# millefori.net
KiCad netlist of a schematic drawn in EAGLE
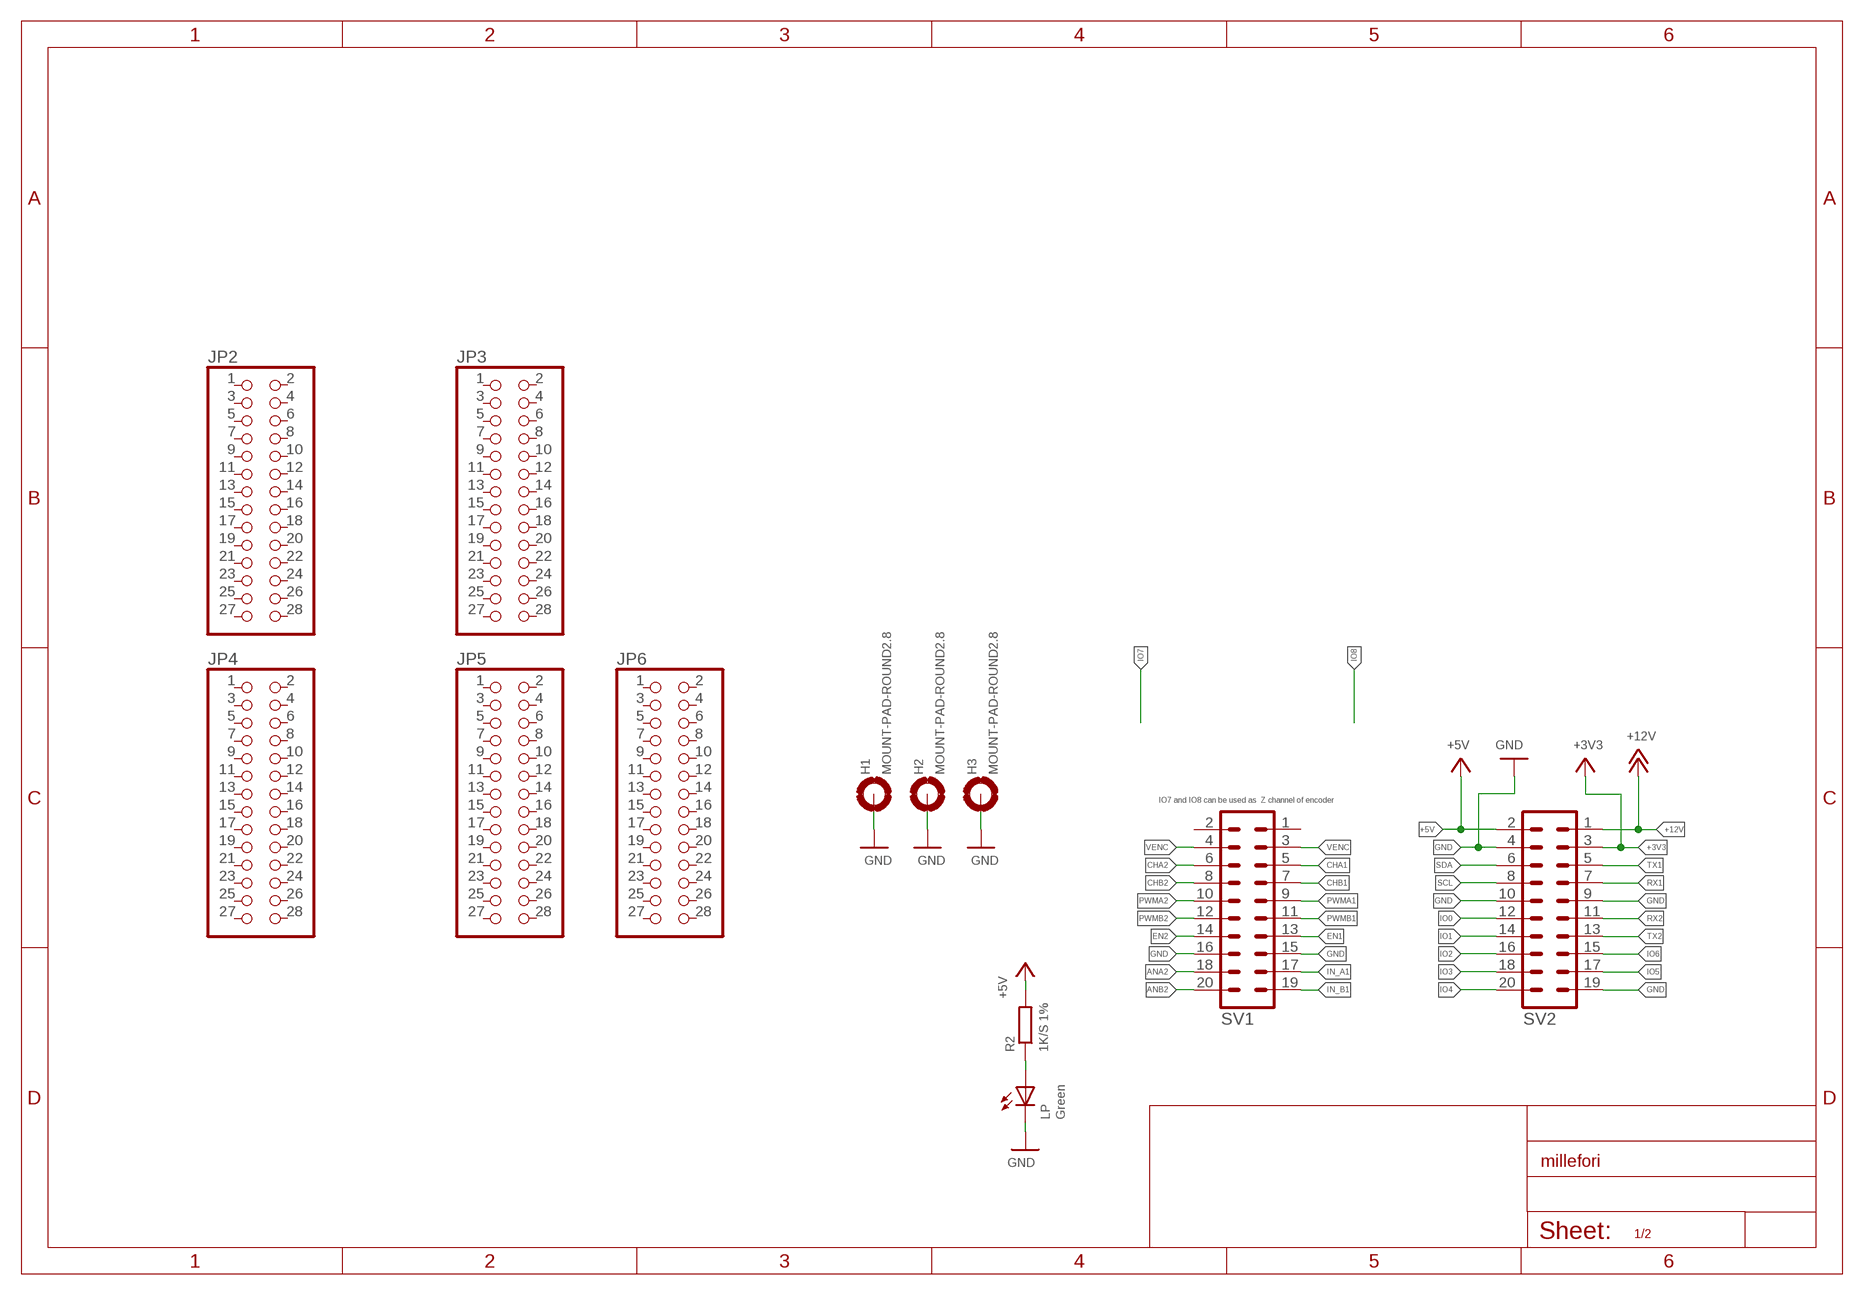
[diagram p0: schematic, sheet 1]
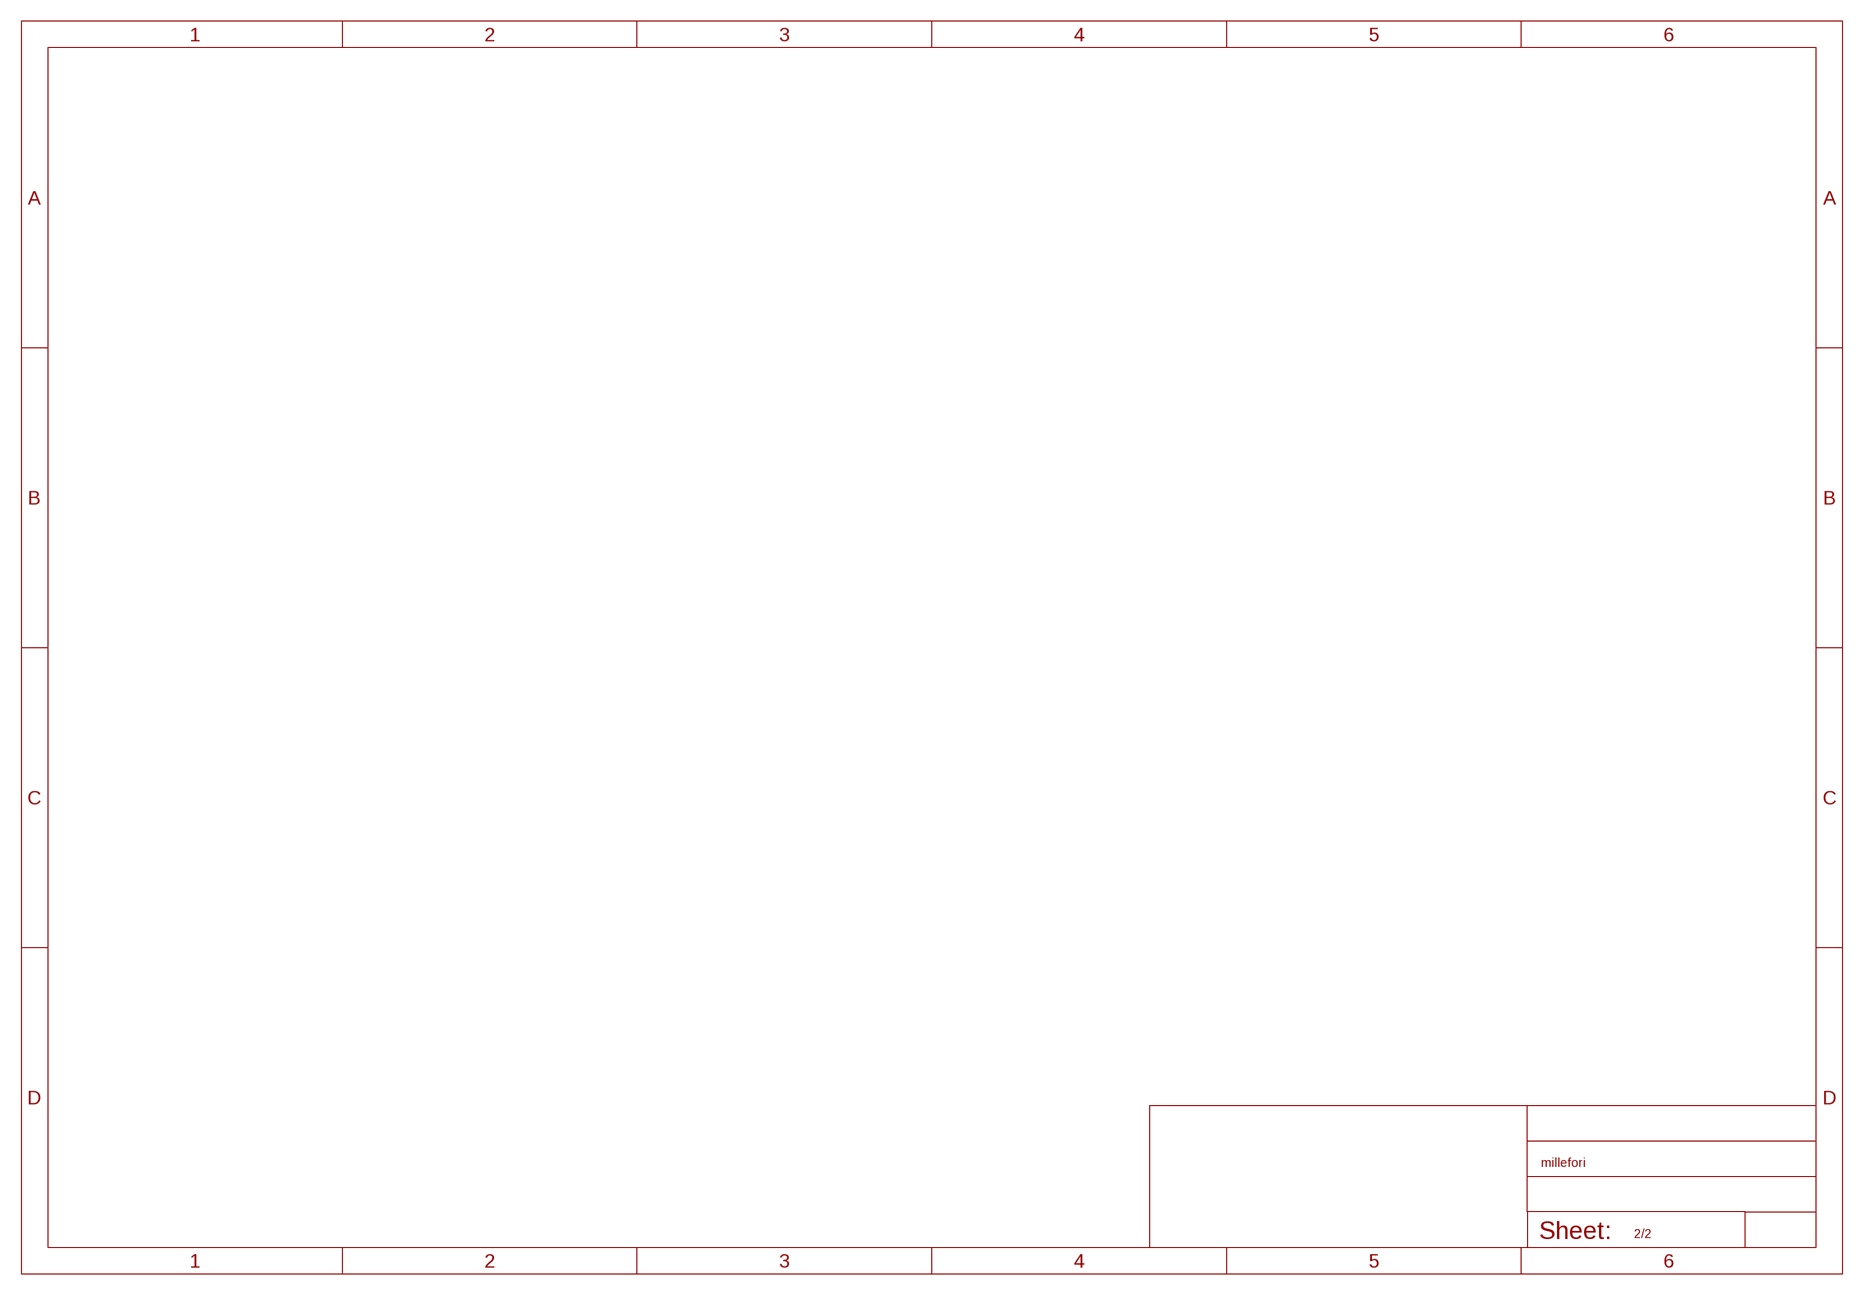
[diagram p1: schematic, sheet 2]

(export (version "E")
  (design (tool "Eeschema 10.0.6"))
  (components
    (comp (ref "H1")
      (value "MOUNT-PAD-ROUND2.8")
      (footprint "eagle-import:2,8-PAD")
      (libsource (lib "eagle-import") (part "MOUNT-PAD-ROUND2.8"))
    )
    (comp (ref "H2")
      (value "MOUNT-PAD-ROUND2.8")
      (footprint "eagle-import:2,8-PAD")
      (libsource (lib "eagle-import") (part "MOUNT-PAD-ROUND2.8"))
    )
    (comp (ref "H3")
      (value "MOUNT-PAD-ROUND2.8")
      (footprint "eagle-import:2,8-PAD")
      (libsource (lib "eagle-import") (part "MOUNT-PAD-ROUND2.8"))
    )
    (comp (ref "JP2")
      (value "PINHD-2X14")
      (footprint "eagle-import:2X14")
      (libsource (lib "eagle-import") (part "PINHD-2X14"))
    )
    (comp (ref "JP3")
      (value "PINHD-2X14")
      (footprint "eagle-import:2X14")
      (libsource (lib "eagle-import") (part "PINHD-2X14"))
    )
    (comp (ref "JP4")
      (value "PINHD-2X14")
      (footprint "eagle-import:2X14")
      (libsource (lib "eagle-import") (part "PINHD-2X14"))
    )
    (comp (ref "JP5")
      (value "PINHD-2X14")
      (footprint "eagle-import:2X14")
      (libsource (lib "eagle-import") (part "PINHD-2X14"))
    )
    (comp (ref "JP6")
      (value "PINHD-2X14")
      (footprint "eagle-import:2X14")
      (libsource (lib "eagle-import") (part "PINHD-2X14"))
    )
    (comp (ref "LP")
      (value "Green")
      (footprint "eagle-import:CHIPLED_0805")
      (libsource (lib "eagle-import") (part "LEDCHIPLED_0805"))
    )
    (comp (ref "R2")
      (value "1K/S 1%")
      (footprint "eagle-import:R0603")
      (libsource (lib "eagle-import") (part "R-EU_R0603"))
    )
    (comp (ref "SV1")
      (value "MA10-2")
      (footprint "eagle-import:MA10-2")
      (fields (field (name "OC_FARNELL") "unknown") (field (name "OC_NEWARK") "unknown"))
      (libsource (lib "eagle-import") (part "MA10-2"))
    )
    (comp (ref "SV2")
      (value "MA10-2")
      (footprint "eagle-import:MA10-2")
      (libsource (lib "eagle-import") (part "MA10-2"))
    )
  )
  (nets
    (net (code "1") (name "+3V3") (class "Default")
      (node (ref "SV2") (pin "3") (pinfunction "3_3") (pintype "passive"))
    )
    (net (code "2") (name "+5V") (class "Default")
      (node (ref "R2") (pin "2") (pinfunction "2_2") (pintype "passive"))
      (node (ref "SV2") (pin "2") (pinfunction "2_2") (pintype "passive"))
    )
    (net (code "3") (name "+12V") (class "Default")
      (node (ref "SV2") (pin "1") (pinfunction "1_1") (pintype "passive"))
    )
    (net (code "4") (name "ANA2") (class "Default")
      (node (ref "SV1") (pin "18") (pinfunction "18_18") (pintype "passive"))
    )
    (net (code "5") (name "ANB2") (class "Default")
      (node (ref "SV1") (pin "20") (pinfunction "20_20") (pintype "passive"))
    )
    (net (code "6") (name "CHA1") (class "Default")
      (node (ref "SV1") (pin "5") (pinfunction "5_5") (pintype "passive"))
    )
    (net (code "7") (name "CHA2") (class "Default")
      (node (ref "SV1") (pin "6") (pinfunction "6_6") (pintype "passive"))
    )
    (net (code "8") (name "CHB1") (class "Default")
      (node (ref "SV1") (pin "7") (pinfunction "7_7") (pintype "passive"))
    )
    (net (code "9") (name "CHB2") (class "Default")
      (node (ref "SV1") (pin "8") (pinfunction "8_8") (pintype "passive"))
    )
    (net (code "10") (name "EN1") (class "Default")
      (node (ref "SV1") (pin "13") (pinfunction "13_13") (pintype "passive"))
    )
    (net (code "11") (name "EN2") (class "Default")
      (node (ref "SV1") (pin "14") (pinfunction "14_14") (pintype "passive"))
    )
    (net (code "12") (name "GND") (class "Default")
      (node (ref "H1") (pin "B2,8") (pinfunction "MOUNT_B2,8") (pintype "passive"))
      (node (ref "H2") (pin "B2,8") (pinfunction "MOUNT_B2,8") (pintype "passive"))
      (node (ref "H3") (pin "B2,8") (pinfunction "MOUNT_B2,8") (pintype "passive"))
      (node (ref "LP") (pin "C") (pinfunction "C_C") (pintype "passive"))
      (node (ref "SV1") (pin "15") (pinfunction "15_15") (pintype "passive"))
      (node (ref "SV1") (pin "16") (pinfunction "16_16") (pintype "passive"))
      (node (ref "SV2") (pin "10") (pinfunction "10_10") (pintype "passive"))
      (node (ref "SV2") (pin "19") (pinfunction "19_19") (pintype "passive"))
      (node (ref "SV2") (pin "4") (pinfunction "4_4") (pintype "passive"))
      (node (ref "SV2") (pin "9") (pinfunction "9_9") (pintype "passive"))
    )
    (net (code "13") (name "IN_A1") (class "Default")
      (node (ref "SV1") (pin "17") (pinfunction "17_17") (pintype "passive"))
    )
    (net (code "14") (name "IN_B1") (class "Default")
      (node (ref "SV1") (pin "19") (pinfunction "19_19") (pintype "passive"))
    )
    (net (code "15") (name "IO0") (class "Default")
      (node (ref "SV2") (pin "12") (pinfunction "12_12") (pintype "passive"))
    )
    (net (code "16") (name "IO1") (class "Default")
      (node (ref "SV2") (pin "14") (pinfunction "14_14") (pintype "passive"))
    )
    (net (code "17") (name "IO2") (class "Default")
      (node (ref "SV2") (pin "16") (pinfunction "16_16") (pintype "passive"))
    )
    (net (code "18") (name "IO3") (class "Default")
      (node (ref "SV2") (pin "18") (pinfunction "18_18") (pintype "passive"))
    )
    (net (code "19") (name "IO4") (class "Default")
      (node (ref "SV2") (pin "20") (pinfunction "20_20") (pintype "passive"))
    )
    (net (code "20") (name "IO5") (class "Default")
      (node (ref "SV2") (pin "17") (pinfunction "17_17") (pintype "passive"))
    )
    (net (code "21") (name "IO6") (class "Default")
      (node (ref "SV2") (pin "15") (pinfunction "15_15") (pintype "passive"))
    )
    (net (code "24") (name "Net-(LP-PadA)") (class "Default")
      (node (ref "LP") (pin "A") (pinfunction "A_A") (pintype "passive"))
      (node (ref "R2") (pin "1") (pinfunction "1_1") (pintype "passive"))
    )
    (net (code "25") (name "PWMA1") (class "Default")
      (node (ref "SV1") (pin "9") (pinfunction "9_9") (pintype "passive"))
    )
    (net (code "26") (name "PWMA2") (class "Default")
      (node (ref "SV1") (pin "10") (pinfunction "10_10") (pintype "passive"))
    )
    (net (code "27") (name "PWMB1") (class "Default")
      (node (ref "SV1") (pin "11") (pinfunction "11_11") (pintype "passive"))
    )
    (net (code "28") (name "PWMB2") (class "Default")
      (node (ref "SV1") (pin "12") (pinfunction "12_12") (pintype "passive"))
    )
    (net (code "29") (name "RX1") (class "Default")
      (node (ref "SV2") (pin "7") (pinfunction "7_7") (pintype "passive"))
    )
    (net (code "30") (name "RX2") (class "Default")
      (node (ref "SV2") (pin "11") (pinfunction "11_11") (pintype "passive"))
    )
    (net (code "31") (name "SCL") (class "Default")
      (node (ref "SV2") (pin "8") (pinfunction "8_8") (pintype "passive"))
    )
    (net (code "32") (name "SDA") (class "Default")
      (node (ref "SV2") (pin "6") (pinfunction "6_6") (pintype "passive"))
    )
    (net (code "33") (name "TX1") (class "Default")
      (node (ref "SV2") (pin "5") (pinfunction "5_5") (pintype "passive"))
    )
    (net (code "34") (name "TX2") (class "Default")
      (node (ref "SV2") (pin "13") (pinfunction "13_13") (pintype "passive"))
    )
    (net (code "35") (name "VENC") (class "Default")
      (node (ref "SV1") (pin "3") (pinfunction "3_3") (pintype "passive"))
      (node (ref "SV1") (pin "4") (pinfunction "4_4") (pintype "passive"))
    )
    (net (code "36") (name "unconnected-(JP2-Pad1)") (class "Default")
      (node (ref "JP2") (pin "1") (pinfunction "1_1") (pintype "passive"))
    )
    (net (code "37") (name "unconnected-(JP2-Pad2)") (class "Default")
      (node (ref "JP2") (pin "2") (pinfunction "2_2") (pintype "passive"))
    )
    (net (code "38") (name "unconnected-(JP2-Pad3)") (class "Default")
      (node (ref "JP2") (pin "3") (pinfunction "3_3") (pintype "passive"))
    )
    (net (code "39") (name "unconnected-(JP2-Pad4)") (class "Default")
      (node (ref "JP2") (pin "4") (pinfunction "4_4") (pintype "passive"))
    )
    (net (code "40") (name "unconnected-(JP2-Pad5)") (class "Default")
      (node (ref "JP2") (pin "5") (pinfunction "5_5") (pintype "passive"))
    )
    (net (code "41") (name "unconnected-(JP2-Pad6)") (class "Default")
      (node (ref "JP2") (pin "6") (pinfunction "6_6") (pintype "passive"))
    )
    (net (code "42") (name "unconnected-(JP2-Pad7)") (class "Default")
      (node (ref "JP2") (pin "7") (pinfunction "7_7") (pintype "passive"))
    )
    (net (code "43") (name "unconnected-(JP2-Pad8)") (class "Default")
      (node (ref "JP2") (pin "8") (pinfunction "8_8") (pintype "passive"))
    )
    (net (code "44") (name "unconnected-(JP2-Pad9)") (class "Default")
      (node (ref "JP2") (pin "9") (pinfunction "9_9") (pintype "passive"))
    )
    (net (code "45") (name "unconnected-(JP2-Pad10)") (class "Default")
      (node (ref "JP2") (pin "10") (pinfunction "10_10") (pintype "passive"))
    )
    (net (code "46") (name "unconnected-(JP2-Pad11)") (class "Default")
      (node (ref "JP2") (pin "11") (pinfunction "11_11") (pintype "passive"))
    )
    (net (code "47") (name "unconnected-(JP2-Pad12)") (class "Default")
      (node (ref "JP2") (pin "12") (pinfunction "12_12") (pintype "passive"))
    )
    (net (code "48") (name "unconnected-(JP2-Pad13)") (class "Default")
      (node (ref "JP2") (pin "13") (pinfunction "13_13") (pintype "passive"))
    )
    (net (code "49") (name "unconnected-(JP2-Pad14)") (class "Default")
      (node (ref "JP2") (pin "14") (pinfunction "14_14") (pintype "passive"))
    )
    (net (code "50") (name "unconnected-(JP2-Pad15)") (class "Default")
      (node (ref "JP2") (pin "15") (pinfunction "15_15") (pintype "passive"))
    )
    (net (code "51") (name "unconnected-(JP2-Pad16)") (class "Default")
      (node (ref "JP2") (pin "16") (pinfunction "16_16") (pintype "passive"))
    )
    (net (code "52") (name "unconnected-(JP2-Pad17)") (class "Default")
      (node (ref "JP2") (pin "17") (pinfunction "17_17") (pintype "passive"))
    )
    (net (code "53") (name "unconnected-(JP2-Pad18)") (class "Default")
      (node (ref "JP2") (pin "18") (pinfunction "18_18") (pintype "passive"))
    )
    (net (code "54") (name "unconnected-(JP2-Pad19)") (class "Default")
      (node (ref "JP2") (pin "19") (pinfunction "19_19") (pintype "passive"))
    )
    (net (code "55") (name "unconnected-(JP2-Pad20)") (class "Default")
      (node (ref "JP2") (pin "20") (pinfunction "20_20") (pintype "passive"))
    )
    (net (code "56") (name "unconnected-(JP2-Pad21)") (class "Default")
      (node (ref "JP2") (pin "21") (pinfunction "21_21") (pintype "passive"))
    )
    (net (code "57") (name "unconnected-(JP2-Pad22)") (class "Default")
      (node (ref "JP2") (pin "22") (pinfunction "22_22") (pintype "passive"))
    )
    (net (code "58") (name "unconnected-(JP2-Pad23)") (class "Default")
      (node (ref "JP2") (pin "23") (pinfunction "23_23") (pintype "passive"))
    )
    (net (code "59") (name "unconnected-(JP2-Pad24)") (class "Default")
      (node (ref "JP2") (pin "24") (pinfunction "24_24") (pintype "passive"))
    )
    (net (code "60") (name "unconnected-(JP2-Pad25)") (class "Default")
      (node (ref "JP2") (pin "25") (pinfunction "25_25") (pintype "passive"))
    )
    (net (code "61") (name "unconnected-(JP2-Pad26)") (class "Default")
      (node (ref "JP2") (pin "26") (pinfunction "26_26") (pintype "passive"))
    )
    (net (code "62") (name "unconnected-(JP2-Pad27)") (class "Default")
      (node (ref "JP2") (pin "27") (pinfunction "27_27") (pintype "passive"))
    )
    (net (code "63") (name "unconnected-(JP2-Pad28)") (class "Default")
      (node (ref "JP2") (pin "28") (pinfunction "28_28") (pintype "passive"))
    )
    (net (code "64") (name "unconnected-(JP3-Pad1)") (class "Default")
      (node (ref "JP3") (pin "1") (pinfunction "1_1") (pintype "passive"))
    )
    (net (code "65") (name "unconnected-(JP3-Pad2)") (class "Default")
      (node (ref "JP3") (pin "2") (pinfunction "2_2") (pintype "passive"))
    )
    (net (code "66") (name "unconnected-(JP3-Pad3)") (class "Default")
      (node (ref "JP3") (pin "3") (pinfunction "3_3") (pintype "passive"))
    )
    (net (code "67") (name "unconnected-(JP3-Pad4)") (class "Default")
      (node (ref "JP3") (pin "4") (pinfunction "4_4") (pintype "passive"))
    )
    (net (code "68") (name "unconnected-(JP3-Pad5)") (class "Default")
      (node (ref "JP3") (pin "5") (pinfunction "5_5") (pintype "passive"))
    )
    (net (code "69") (name "unconnected-(JP3-Pad6)") (class "Default")
      (node (ref "JP3") (pin "6") (pinfunction "6_6") (pintype "passive"))
    )
    (net (code "70") (name "unconnected-(JP3-Pad7)") (class "Default")
      (node (ref "JP3") (pin "7") (pinfunction "7_7") (pintype "passive"))
    )
    (net (code "71") (name "unconnected-(JP3-Pad8)") (class "Default")
      (node (ref "JP3") (pin "8") (pinfunction "8_8") (pintype "passive"))
    )
    (net (code "72") (name "unconnected-(JP3-Pad9)") (class "Default")
      (node (ref "JP3") (pin "9") (pinfunction "9_9") (pintype "passive"))
    )
    (net (code "73") (name "unconnected-(JP3-Pad10)") (class "Default")
      (node (ref "JP3") (pin "10") (pinfunction "10_10") (pintype "passive"))
    )
    (net (code "74") (name "unconnected-(JP3-Pad11)") (class "Default")
      (node (ref "JP3") (pin "11") (pinfunction "11_11") (pintype "passive"))
    )
    (net (code "75") (name "unconnected-(JP3-Pad12)") (class "Default")
      (node (ref "JP3") (pin "12") (pinfunction "12_12") (pintype "passive"))
    )
    (net (code "76") (name "unconnected-(JP3-Pad13)") (class "Default")
      (node (ref "JP3") (pin "13") (pinfunction "13_13") (pintype "passive"))
    )
    (net (code "77") (name "unconnected-(JP3-Pad14)") (class "Default")
      (node (ref "JP3") (pin "14") (pinfunction "14_14") (pintype "passive"))
    )
    (net (code "78") (name "unconnected-(JP3-Pad15)") (class "Default")
      (node (ref "JP3") (pin "15") (pinfunction "15_15") (pintype "passive"))
    )
    (net (code "79") (name "unconnected-(JP3-Pad16)") (class "Default")
      (node (ref "JP3") (pin "16") (pinfunction "16_16") (pintype "passive"))
    )
    (net (code "80") (name "unconnected-(JP3-Pad17)") (class "Default")
      (node (ref "JP3") (pin "17") (pinfunction "17_17") (pintype "passive"))
    )
    (net (code "81") (name "unconnected-(JP3-Pad18)") (class "Default")
      (node (ref "JP3") (pin "18") (pinfunction "18_18") (pintype "passive"))
    )
    (net (code "82") (name "unconnected-(JP3-Pad19)") (class "Default")
      (node (ref "JP3") (pin "19") (pinfunction "19_19") (pintype "passive"))
    )
    (net (code "83") (name "unconnected-(JP3-Pad20)") (class "Default")
      (node (ref "JP3") (pin "20") (pinfunction "20_20") (pintype "passive"))
    )
    (net (code "84") (name "unconnected-(JP3-Pad21)") (class "Default")
      (node (ref "JP3") (pin "21") (pinfunction "21_21") (pintype "passive"))
    )
    (net (code "85") (name "unconnected-(JP3-Pad22)") (class "Default")
      (node (ref "JP3") (pin "22") (pinfunction "22_22") (pintype "passive"))
    )
    (net (code "86") (name "unconnected-(JP3-Pad23)") (class "Default")
      (node (ref "JP3") (pin "23") (pinfunction "23_23") (pintype "passive"))
    )
    (net (code "87") (name "unconnected-(JP3-Pad24)") (class "Default")
      (node (ref "JP3") (pin "24") (pinfunction "24_24") (pintype "passive"))
    )
    (net (code "88") (name "unconnected-(JP3-Pad25)") (class "Default")
      (node (ref "JP3") (pin "25") (pinfunction "25_25") (pintype "passive"))
    )
    (net (code "89") (name "unconnected-(JP3-Pad26)") (class "Default")
      (node (ref "JP3") (pin "26") (pinfunction "26_26") (pintype "passive"))
    )
    (net (code "90") (name "unconnected-(JP3-Pad27)") (class "Default")
      (node (ref "JP3") (pin "27") (pinfunction "27_27") (pintype "passive"))
    )
    (net (code "91") (name "unconnected-(JP3-Pad28)") (class "Default")
      (node (ref "JP3") (pin "28") (pinfunction "28_28") (pintype "passive"))
    )
    (net (code "92") (name "unconnected-(JP4-Pad1)") (class "Default")
      (node (ref "JP4") (pin "1") (pinfunction "1_1") (pintype "passive"))
    )
    (net (code "93") (name "unconnected-(JP4-Pad2)") (class "Default")
      (node (ref "JP4") (pin "2") (pinfunction "2_2") (pintype "passive"))
    )
    (net (code "94") (name "unconnected-(JP4-Pad3)") (class "Default")
      (node (ref "JP4") (pin "3") (pinfunction "3_3") (pintype "passive"))
    )
    (net (code "95") (name "unconnected-(JP4-Pad4)") (class "Default")
      (node (ref "JP4") (pin "4") (pinfunction "4_4") (pintype "passive"))
    )
    (net (code "96") (name "unconnected-(JP4-Pad5)") (class "Default")
      (node (ref "JP4") (pin "5") (pinfunction "5_5") (pintype "passive"))
    )
    (net (code "97") (name "unconnected-(JP4-Pad6)") (class "Default")
      (node (ref "JP4") (pin "6") (pinfunction "6_6") (pintype "passive"))
    )
    (net (code "98") (name "unconnected-(JP4-Pad7)") (class "Default")
      (node (ref "JP4") (pin "7") (pinfunction "7_7") (pintype "passive"))
    )
    (net (code "99") (name "unconnected-(JP4-Pad8)") (class "Default")
      (node (ref "JP4") (pin "8") (pinfunction "8_8") (pintype "passive"))
    )
    (net (code "100") (name "unconnected-(JP4-Pad9)") (class "Default")
      (node (ref "JP4") (pin "9") (pinfunction "9_9") (pintype "passive"))
    )
    (net (code "101") (name "unconnected-(JP4-Pad10)") (class "Default")
      (node (ref "JP4") (pin "10") (pinfunction "10_10") (pintype "passive"))
    )
    (net (code "102") (name "unconnected-(JP4-Pad11)") (class "Default")
      (node (ref "JP4") (pin "11") (pinfunction "11_11") (pintype "passive"))
    )
    (net (code "103") (name "unconnected-(JP4-Pad12)") (class "Default")
      (node (ref "JP4") (pin "12") (pinfunction "12_12") (pintype "passive"))
    )
    (net (code "104") (name "unconnected-(JP4-Pad13)") (class "Default")
      (node (ref "JP4") (pin "13") (pinfunction "13_13") (pintype "passive"))
    )
    (net (code "105") (name "unconnected-(JP4-Pad14)") (class "Default")
      (node (ref "JP4") (pin "14") (pinfunction "14_14") (pintype "passive"))
    )
    (net (code "106") (name "unconnected-(JP4-Pad15)") (class "Default")
      (node (ref "JP4") (pin "15") (pinfunction "15_15") (pintype "passive"))
    )
    (net (code "107") (name "unconnected-(JP4-Pad16)") (class "Default")
      (node (ref "JP4") (pin "16") (pinfunction "16_16") (pintype "passive"))
    )
    (net (code "108") (name "unconnected-(JP4-Pad17)") (class "Default")
      (node (ref "JP4") (pin "17") (pinfunction "17_17") (pintype "passive"))
    )
    (net (code "109") (name "unconnected-(JP4-Pad18)") (class "Default")
      (node (ref "JP4") (pin "18") (pinfunction "18_18") (pintype "passive"))
    )
    (net (code "110") (name "unconnected-(JP4-Pad19)") (class "Default")
      (node (ref "JP4") (pin "19") (pinfunction "19_19") (pintype "passive"))
    )
    (net (code "111") (name "unconnected-(JP4-Pad20)") (class "Default")
      (node (ref "JP4") (pin "20") (pinfunction "20_20") (pintype "passive"))
    )
    (net (code "112") (name "unconnected-(JP4-Pad21)") (class "Default")
      (node (ref "JP4") (pin "21") (pinfunction "21_21") (pintype "passive"))
    )
    (net (code "113") (name "unconnected-(JP4-Pad22)") (class "Default")
      (node (ref "JP4") (pin "22") (pinfunction "22_22") (pintype "passive"))
    )
    (net (code "114") (name "unconnected-(JP4-Pad23)") (class "Default")
      (node (ref "JP4") (pin "23") (pinfunction "23_23") (pintype "passive"))
    )
    (net (code "115") (name "unconnected-(JP4-Pad24)") (class "Default")
      (node (ref "JP4") (pin "24") (pinfunction "24_24") (pintype "passive"))
    )
    (net (code "116") (name "unconnected-(JP4-Pad25)") (class "Default")
      (node (ref "JP4") (pin "25") (pinfunction "25_25") (pintype "passive"))
    )
    (net (code "117") (name "unconnected-(JP4-Pad26)") (class "Default")
      (node (ref "JP4") (pin "26") (pinfunction "26_26") (pintype "passive"))
    )
    (net (code "118") (name "unconnected-(JP4-Pad27)") (class "Default")
      (node (ref "JP4") (pin "27") (pinfunction "27_27") (pintype "passive"))
    )
    (net (code "119") (name "unconnected-(JP4-Pad28)") (class "Default")
      (node (ref "JP4") (pin "28") (pinfunction "28_28") (pintype "passive"))
    )
    (net (code "120") (name "unconnected-(JP5-Pad1)") (class "Default")
      (node (ref "JP5") (pin "1") (pinfunction "1_1") (pintype "passive"))
    )
    (net (code "121") (name "unconnected-(JP5-Pad2)") (class "Default")
      (node (ref "JP5") (pin "2") (pinfunction "2_2") (pintype "passive"))
    )
    (net (code "122") (name "unconnected-(JP5-Pad3)") (class "Default")
      (node (ref "JP5") (pin "3") (pinfunction "3_3") (pintype "passive"))
    )
    (net (code "123") (name "unconnected-(JP5-Pad4)") (class "Default")
      (node (ref "JP5") (pin "4") (pinfunction "4_4") (pintype "passive"))
    )
    (net (code "124") (name "unconnected-(JP5-Pad5)") (class "Default")
      (node (ref "JP5") (pin "5") (pinfunction "5_5") (pintype "passive"))
    )
    (net (code "125") (name "unconnected-(JP5-Pad6)") (class "Default")
      (node (ref "JP5") (pin "6") (pinfunction "6_6") (pintype "passive"))
    )
    (net (code "126") (name "unconnected-(JP5-Pad7)") (class "Default")
      (node (ref "JP5") (pin "7") (pinfunction "7_7") (pintype "passive"))
    )
    (net (code "127") (name "unconnected-(JP5-Pad8)") (class "Default")
      (node (ref "JP5") (pin "8") (pinfunction "8_8") (pintype "passive"))
    )
    (net (code "128") (name "unconnected-(JP5-Pad9)") (class "Default")
      (node (ref "JP5") (pin "9") (pinfunction "9_9") (pintype "passive"))
    )
    (net (code "129") (name "unconnected-(JP5-Pad10)") (class "Default")
      (node (ref "JP5") (pin "10") (pinfunction "10_10") (pintype "passive"))
    )
    (net (code "130") (name "unconnected-(JP5-Pad11)") (class "Default")
      (node (ref "JP5") (pin "11") (pinfunction "11_11") (pintype "passive"))
    )
    (net (code "131") (name "unconnected-(JP5-Pad12)") (class "Default")
      (node (ref "JP5") (pin "12") (pinfunction "12_12") (pintype "passive"))
    )
    (net (code "132") (name "unconnected-(JP5-Pad13)") (class "Default")
      (node (ref "JP5") (pin "13") (pinfunction "13_13") (pintype "passive"))
    )
    (net (code "133") (name "unconnected-(JP5-Pad14)") (class "Default")
      (node (ref "JP5") (pin "14") (pinfunction "14_14") (pintype "passive"))
    )
    (net (code "134") (name "unconnected-(JP5-Pad15)") (class "Default")
      (node (ref "JP5") (pin "15") (pinfunction "15_15") (pintype "passive"))
    )
    (net (code "135") (name "unconnected-(JP5-Pad16)") (class "Default")
      (node (ref "JP5") (pin "16") (pinfunction "16_16") (pintype "passive"))
    )
    (net (code "136") (name "unconnected-(JP5-Pad17)") (class "Default")
      (node (ref "JP5") (pin "17") (pinfunction "17_17") (pintype "passive"))
    )
    (net (code "137") (name "unconnected-(JP5-Pad18)") (class "Default")
      (node (ref "JP5") (pin "18") (pinfunction "18_18") (pintype "passive"))
    )
    (net (code "138") (name "unconnected-(JP5-Pad19)") (class "Default")
      (node (ref "JP5") (pin "19") (pinfunction "19_19") (pintype "passive"))
    )
    (net (code "139") (name "unconnected-(JP5-Pad20)") (class "Default")
      (node (ref "JP5") (pin "20") (pinfunction "20_20") (pintype "passive"))
    )
    (net (code "140") (name "unconnected-(JP5-Pad21)") (class "Default")
      (node (ref "JP5") (pin "21") (pinfunction "21_21") (pintype "passive"))
    )
    (net (code "141") (name "unconnected-(JP5-Pad22)") (class "Default")
      (node (ref "JP5") (pin "22") (pinfunction "22_22") (pintype "passive"))
    )
    (net (code "142") (name "unconnected-(JP5-Pad23)") (class "Default")
      (node (ref "JP5") (pin "23") (pinfunction "23_23") (pintype "passive"))
    )
    (net (code "143") (name "unconnected-(JP5-Pad24)") (class "Default")
      (node (ref "JP5") (pin "24") (pinfunction "24_24") (pintype "passive"))
    )
    (net (code "144") (name "unconnected-(JP5-Pad25)") (class "Default")
      (node (ref "JP5") (pin "25") (pinfunction "25_25") (pintype "passive"))
    )
    (net (code "145") (name "unconnected-(JP5-Pad26)") (class "Default")
      (node (ref "JP5") (pin "26") (pinfunction "26_26") (pintype "passive"))
    )
    (net (code "146") (name "unconnected-(JP5-Pad27)") (class "Default")
      (node (ref "JP5") (pin "27") (pinfunction "27_27") (pintype "passive"))
    )
    (net (code "147") (name "unconnected-(JP5-Pad28)") (class "Default")
      (node (ref "JP5") (pin "28") (pinfunction "28_28") (pintype "passive"))
    )
    (net (code "148") (name "unconnected-(JP6-Pad1)") (class "Default")
      (node (ref "JP6") (pin "1") (pinfunction "1_1") (pintype "passive"))
    )
    (net (code "149") (name "unconnected-(JP6-Pad2)") (class "Default")
      (node (ref "JP6") (pin "2") (pinfunction "2_2") (pintype "passive"))
    )
    (net (code "150") (name "unconnected-(JP6-Pad3)") (class "Default")
      (node (ref "JP6") (pin "3") (pinfunction "3_3") (pintype "passive"))
    )
    (net (code "151") (name "unconnected-(JP6-Pad4)") (class "Default")
      (node (ref "JP6") (pin "4") (pinfunction "4_4") (pintype "passive"))
    )
    (net (code "152") (name "unconnected-(JP6-Pad5)") (class "Default")
      (node (ref "JP6") (pin "5") (pinfunction "5_5") (pintype "passive"))
    )
    (net (code "153") (name "unconnected-(JP6-Pad6)") (class "Default")
      (node (ref "JP6") (pin "6") (pinfunction "6_6") (pintype "passive"))
    )
    (net (code "154") (name "unconnected-(JP6-Pad7)") (class "Default")
      (node (ref "JP6") (pin "7") (pinfunction "7_7") (pintype "passive"))
    )
    (net (code "155") (name "unconnected-(JP6-Pad8)") (class "Default")
      (node (ref "JP6") (pin "8") (pinfunction "8_8") (pintype "passive"))
    )
    (net (code "156") (name "unconnected-(JP6-Pad9)") (class "Default")
      (node (ref "JP6") (pin "9") (pinfunction "9_9") (pintype "passive"))
    )
    (net (code "157") (name "unconnected-(JP6-Pad10)") (class "Default")
      (node (ref "JP6") (pin "10") (pinfunction "10_10") (pintype "passive"))
    )
    (net (code "158") (name "unconnected-(JP6-Pad11)") (class "Default")
      (node (ref "JP6") (pin "11") (pinfunction "11_11") (pintype "passive"))
    )
    (net (code "159") (name "unconnected-(JP6-Pad12)") (class "Default")
      (node (ref "JP6") (pin "12") (pinfunction "12_12") (pintype "passive"))
    )
    (net (code "160") (name "unconnected-(JP6-Pad13)") (class "Default")
      (node (ref "JP6") (pin "13") (pinfunction "13_13") (pintype "passive"))
    )
    (net (code "161") (name "unconnected-(JP6-Pad14)") (class "Default")
      (node (ref "JP6") (pin "14") (pinfunction "14_14") (pintype "passive"))
    )
    (net (code "162") (name "unconnected-(JP6-Pad15)") (class "Default")
      (node (ref "JP6") (pin "15") (pinfunction "15_15") (pintype "passive"))
    )
    (net (code "163") (name "unconnected-(JP6-Pad16)") (class "Default")
      (node (ref "JP6") (pin "16") (pinfunction "16_16") (pintype "passive"))
    )
    (net (code "164") (name "unconnected-(JP6-Pad17)") (class "Default")
      (node (ref "JP6") (pin "17") (pinfunction "17_17") (pintype "passive"))
    )
    (net (code "165") (name "unconnected-(JP6-Pad18)") (class "Default")
      (node (ref "JP6") (pin "18") (pinfunction "18_18") (pintype "passive"))
    )
    (net (code "166") (name "unconnected-(JP6-Pad19)") (class "Default")
      (node (ref "JP6") (pin "19") (pinfunction "19_19") (pintype "passive"))
    )
    (net (code "167") (name "unconnected-(JP6-Pad20)") (class "Default")
      (node (ref "JP6") (pin "20") (pinfunction "20_20") (pintype "passive"))
    )
    (net (code "168") (name "unconnected-(JP6-Pad21)") (class "Default")
      (node (ref "JP6") (pin "21") (pinfunction "21_21") (pintype "passive"))
    )
    (net (code "169") (name "unconnected-(JP6-Pad22)") (class "Default")
      (node (ref "JP6") (pin "22") (pinfunction "22_22") (pintype "passive"))
    )
    (net (code "170") (name "unconnected-(JP6-Pad23)") (class "Default")
      (node (ref "JP6") (pin "23") (pinfunction "23_23") (pintype "passive"))
    )
    (net (code "171") (name "unconnected-(JP6-Pad24)") (class "Default")
      (node (ref "JP6") (pin "24") (pinfunction "24_24") (pintype "passive"))
    )
    (net (code "172") (name "unconnected-(JP6-Pad25)") (class "Default")
      (node (ref "JP6") (pin "25") (pinfunction "25_25") (pintype "passive"))
    )
    (net (code "173") (name "unconnected-(JP6-Pad26)") (class "Default")
      (node (ref "JP6") (pin "26") (pinfunction "26_26") (pintype "passive"))
    )
    (net (code "174") (name "unconnected-(JP6-Pad27)") (class "Default")
      (node (ref "JP6") (pin "27") (pinfunction "27_27") (pintype "passive"))
    )
    (net (code "175") (name "unconnected-(JP6-Pad28)") (class "Default")
      (node (ref "JP6") (pin "28") (pinfunction "28_28") (pintype "passive"))
    )
    (net (code "176") (name "unconnected-(SV1-Pad1)") (class "Default")
      (node (ref "SV1") (pin "1") (pinfunction "1_1") (pintype "passive"))
    )
    (net (code "177") (name "unconnected-(SV1-Pad2)") (class "Default")
      (node (ref "SV1") (pin "2") (pinfunction "2_2") (pintype "passive"))
    )
  )
)
